# power.net
KiCad netlist of a schematic drawn in Altium Designer
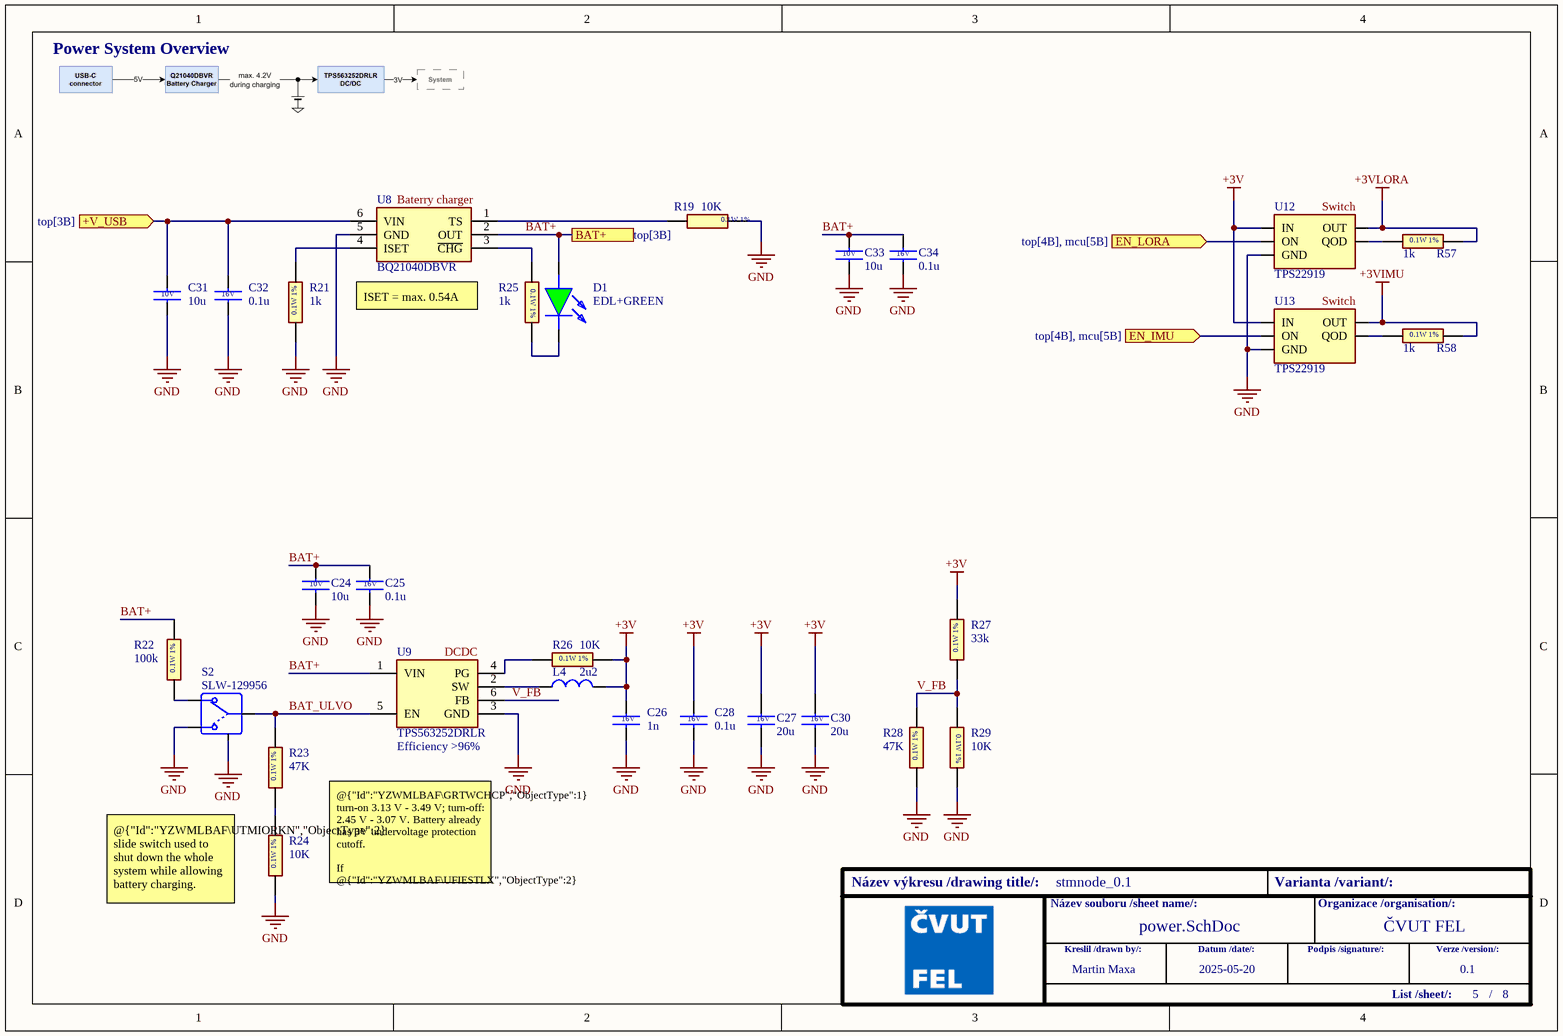
[diagram p0: power.SchDoc]

(export (version "E")
  (design (tool "Eeschema 10.0.6"))
  (components
    (comp (ref "C24")
      (value "10u")
      (footprint "C0603")
      (description "10 VDC, 20 %, X5R")
      (fields
        (field (name "MANUFACTURER_PART_NUMBER") "C0603C106M8PACTU")
        (field (name "MOUSER PART NUMBER") "80-C0603C106M8PACTU")
      )
      (libsource (lib "bch-lib") (part "ECK+10u10V"))
    )
    (comp (ref "C25")
      (value "0.1u")
      (footprint "CAPC1608X95N")
      (description "16V 0.1uF XR7 0603 10%")
      (fields
        (field (name "MANUFACTURER_PART_NUMBER") "C0603C104K4RAC-TU")
        (field (name "MOUSER PART NUMBER") "80-C0603C104K4RAC")
      )
      (libsource (lib "bch-lib") (part "ECK+100n16V"))
    )
    (comp (ref "C26")
      (value "1n")
      (footprint "CAPC1608X87N")
      (description "16 VDC, 10 %, X7R")
      (fields (field (name "MANUFACTURER_PART_NUMBER") "C0603C102K4RECTU"))
      (libsource (lib "bch-lib") (part "ECK+1n16V"))
    )
    (comp (ref "C27")
      (value "20u")
      (footprint "C0603")
      (description "Capacitor")
      (fields
        (field (name "MANUFACTURER_PART_NUMBER") "C0603C200K4HACAUTO")
        (field (name "MOUSER PART NUMBER") "80-C0603C200K4HAUTO")
      )
      (libsource (lib "bch-lib") (part "ECK+20u16V"))
    )
    (comp (ref "C28")
      (value "0.1u")
      (footprint "CAPC1608X95N")
      (description "16V 0.1uF XR7 0603 10%")
      (fields
        (field (name "MANUFACTURER_PART_NUMBER") "C0603C104K4RAC-TU")
        (field (name "MOUSER PART NUMBER") "80-C0603C104K4RAC")
      )
      (libsource (lib "bch-lib") (part "ECK+100n16V"))
    )
    (comp (ref "C30")
      (value "20u")
      (footprint "C0603")
      (description "Capacitor")
      (fields
        (field (name "MANUFACTURER_PART_NUMBER") "C0603C200K4HACAUTO")
        (field (name "MOUSER PART NUMBER") "80-C0603C200K4HAUTO")
      )
      (libsource (lib "bch-lib") (part "ECK+20u16V"))
    )
    (comp (ref "C31")
      (value "10u")
      (footprint "C0603")
      (description "10 VDC, 20 %, X5R")
      (fields
        (field (name "MANUFACTURER_PART_NUMBER") "C0603C106M8PACTU")
        (field (name "MOUSER PART NUMBER") "80-C0603C106M8PACTU")
      )
      (libsource (lib "bch-lib") (part "ECK+10u10V"))
    )
    (comp (ref "C32")
      (value "0.1u")
      (footprint "CAPC1608X95N")
      (description "16V 0.1uF XR7 0603 10%")
      (fields
        (field (name "MANUFACTURER_PART_NUMBER") "C0603C104K4RAC-TU")
        (field (name "MOUSER PART NUMBER") "80-C0603C104K4RAC")
      )
      (libsource (lib "bch-lib") (part "ECK+100n16V"))
    )
    (comp (ref "C33")
      (value "10u")
      (footprint "C0603")
      (description "10 VDC, 20 %, X5R")
      (fields
        (field (name "MANUFACTURER_PART_NUMBER") "C0603C106M8PACTU")
        (field (name "MOUSER PART NUMBER") "80-C0603C106M8PACTU")
      )
      (libsource (lib "bch-lib") (part "ECK+10u10V"))
    )
    (comp (ref "C34")
      (value "0.1u")
      (footprint "CAPC1608X95N")
      (description "16V 0.1uF XR7 0603 10%")
      (fields
        (field (name "MANUFACTURER_PART_NUMBER") "C0603C104K4RAC-TU")
        (field (name "MOUSER PART NUMBER") "80-C0603C104K4RAC")
      )
      (libsource (lib "bch-lib") (part "ECK+100n16V"))
    )
    (comp (ref "D1")
      (value "EDL+GREEN")
      (footprint "LEDM2012X80N")
      (description "LED GREEN,  3.2 V")
      (fields
        (field (name "MANUFACTURER_PART_NUMBER") "150080GS75000")
        (field (name "MOUSER PART NUMBER") "710-150080GS75000")
      )
      (libsource (lib "bch-lib") (part "EDL+GREEN"))
    )
    (comp (ref "L4")
      (value "2u2")
      (footprint "INDPM5752X300N")
      (description "Power Inductors - SMD 2.2uH 20%")
      (fields
        (field (name "MANUFACTURER_PART_NUMBER") "SRP5030TA-2R2M")
        (field (name "MOUSER PART NUMBER") "652-SRP5030TA-2R2M")
      )
      (libsource (lib "bch-lib") (part "EL+2.2u5.5A"))
    )
    (comp (ref "R19")
      (value "10K")
      (footprint "RESC1608X50N")
      (description "Resistor 1%, 0.1W")
      (fields
        (field (name "MANUFACTURER_PART_NUMBER") "CRCW060310K0FKEA")
        (field (name "MOUSER PART NUMBER") "71-CRCW0603-10K-E3")
      )
      (libsource (lib "bch-lib") (part "ER+10K"))
    )
    (comp (ref "R21")
      (value "1k")
      (footprint "RESC1608X50N")
      (description "Resistor 1%, 0.1W")
      (fields
        (field (name "MANUFACTURER_PART_NUMBER") "CRCW06031K00FKEA")
        (field (name "MOUSER PART NUMBER") "71-CRCW0603-1.0K-E3")
      )
      (libsource (lib "") (part "ER+1K_1"))
    )
    (comp (ref "R22")
      (value "100k")
      (footprint "RESC1608X55N")
      (description "Thick Film Resistors 0603 - SMD 1/10Watt 100Kohms 1% Commercial Use")
      (fields
        (field (name "MANUFACTURER_PART_NUMBER") "AC0603FR-10100KL")
        (field (name "MOUSER PART NUMBER") "603-AC0603FR-10100KL")
      )
      (libsource (lib "bch-lib") (part "ER+100k"))
    )
    (comp (ref "R23")
      (value "47K")
      (footprint "RESC1608X50N")
      (description "Resistor 1%, 0.1W")
      (fields
        (field (name "MANUFACTURER_PART_NUMBER") "CRCW060347K0FKEA")
        (field (name "MOUSER PART NUMBER") "71-CRCW0603-47K-E3")
      )
      (libsource (lib "bch-lib") (part "ER+47K"))
    )
    (comp (ref "R24")
      (value "10K")
      (footprint "RESC1608X50N")
      (description "Resistor 1%, 0.1W")
      (fields
        (field (name "MANUFACTURER_PART_NUMBER") "CRCW060310K0FKEA")
        (field (name "MOUSER PART NUMBER") "71-CRCW0603-10K-E3")
      )
      (libsource (lib "") (part "ER+10K_2"))
    )
    (comp (ref "R25")
      (value "1k")
      (footprint "RESC1608X50N")
      (description "Resistor 1%, 0.1W")
      (fields
        (field (name "MANUFACTURER_PART_NUMBER") "CRCW06031K00FKEA")
        (field (name "MOUSER PART NUMBER") "71-CRCW0603-1.0K-E3")
      )
      (libsource (lib "bch-lib") (part "ER+1K"))
    )
    (comp (ref "R26")
      (value "10K")
      (footprint "RESC1608X50N")
      (description "Resistor 1%, 0.1W")
      (fields
        (field (name "MANUFACTURER_PART_NUMBER") "CRCW060310K0FKEA")
        (field (name "MOUSER PART NUMBER") "71-CRCW0603-10K-E3")
      )
      (libsource (lib "") (part "ER+10K_1"))
    )
    (comp (ref "R27")
      (value "33k")
      (footprint "RESC1608X55N")
      (description "Thick Film Resistors - SMD General Purpose Chip Resistor 0603, 33kOhms, 1%, 1/10W")
      (fields
        (field (name "MANUFACTURER_PART_NUMBER") "RC0603FR-1333KL")
        (field (name "MOUSER PART NUMBER") "603-RC0603FR-1333KL")
      )
      (libsource (lib "bch-lib") (part "ER+33k"))
    )
    (comp (ref "R28")
      (value "47K")
      (footprint "RESC1608X50N")
      (description "Resistor 1%, 0.1W")
      (fields
        (field (name "MANUFACTURER_PART_NUMBER") "CRCW060347K0FKEA")
        (field (name "MOUSER PART NUMBER") "71-CRCW0603-47K-E3")
      )
      (libsource (lib "bch-lib") (part "ER+47K"))
    )
    (comp (ref "R29")
      (value "10K")
      (footprint "RESC1608X50N")
      (description "Resistor 1%, 0.1W")
      (fields
        (field (name "MANUFACTURER_PART_NUMBER") "CRCW060310K0FKEA")
        (field (name "MOUSER PART NUMBER") "71-CRCW0603-10K-E3")
      )
      (libsource (lib "bch-lib") (part "ER+10K"))
    )
    (comp (ref "R57")
      (value "1k")
      (footprint "RESC1608X50N")
      (description "Resistor 1%, 0.1W")
      (fields
        (field (name "MANUFACTURER_PART_NUMBER") "CRCW06031K00FKEA")
        (field (name "MOUSER PART NUMBER") "71-CRCW0603-1.0K-E3")
      )
      (libsource (lib "") (part "ER+1K_2"))
    )
    (comp (ref "R58")
      (value "1k")
      (footprint "RESC1608X50N")
      (description "Resistor 1%, 0.1W")
      (fields
        (field (name "MANUFACTURER_PART_NUMBER") "CRCW06031K00FKEA")
        (field (name "MOUSER PART NUMBER") "71-CRCW0603-1.0K-E3")
      )
      (libsource (lib "") (part "ER+1K_2"))
    )
    (comp (ref "S2")
      (value "SLW-129956")
      (footprint "SLW1299564ARAND")
      (description "Slide Switch, Right Angle, max. 50 VDC, max. 300 mA, ON - ON")
      (fields
        (field (name "MANUFACTURER_PART_NUMBER") "SLW-129956-4A-RA-N-D")
        (field (name "MOUSER PART NUMBER") "179-SLW1299564ARAND")
      )
      (libsource (lib "bch-lib") (part "ESW-SLW-129956"))
    )
    (comp (ref "U8")
      (value "BQ21040DBVR")
      (footprint "SOT95P280X145-6N")
      (description "Battery Management 1-cell 0.8-A Li-ion and Li-polymer batt A 595-BQ21040DBVT")
      (fields (field (name "MOUSER PART NUMBER") "595-BQ21040DBVR"))
      (libsource (lib "bch-lib") (part "EU+BQ21040DBVR"))
    )
    (comp (ref "U9")
      (value "TPS563252DRLR")
      (footprint "SOTFL50P160X60-6N")
      (description "Switching Voltage Regulators 3-V to 17-V input vo ltage 3-A 1.2-Mhz")
      (fields (field (name "MOUSER PART NUMBER") "595-TPS563252DRLR"))
      (libsource (lib "bch-lib") (part "EU+TPS563252DRLR"))
    )
    (comp (ref "U12")
      (value "TPS22919")
      (footprint "SOT65P210X110-6N")
      (description "Power Switch ICs - Power Distribution 1-ch 5.5V 1.5A 90 mOhm self-protected AE")
      (fields
        (field (name "MANUFACTURER_PART_NUMBER") "TPS22919QDCKRQ1")
        (field (name "MOUSER PART NUMBER") "595-TPS22919QDCKRQ1")
      )
      (libsource (lib "bch-lib") (part "EU+TPS22919"))
    )
    (comp (ref "U13")
      (value "TPS22919")
      (footprint "SOT65P210X110-6N")
      (description "Power Switch ICs - Power Distribution 1-ch 5.5V 1.5A 90 mOhm self-protected AE")
      (fields
        (field (name "MANUFACTURER_PART_NUMBER") "TPS22919QDCKRQ1")
        (field (name "MOUSER PART NUMBER") "595-TPS22919QDCKRQ1")
      )
      (libsource (lib "bch-lib") (part "EU+TPS22919"))
    )
  )
  (nets
    (net (code "1") (name "+3V") (class "Default")
      (node (ref "C26") (pin "1") (pinfunction "1_1") (pintype "passive"))
      (node (ref "C27") (pin "1") (pinfunction "1_1") (pintype "passive"))
      (node (ref "C28") (pin "1") (pinfunction "1_1") (pintype "passive"))
      (node (ref "C30") (pin "1") (pinfunction "1_1") (pintype "passive"))
      (node (ref "L4") (pin "2") (pinfunction "2_2") (pintype "passive"))
      (node (ref "R26") (pin "2") (pinfunction "2_2") (pintype "passive"))
      (node (ref "R27") (pin "2") (pinfunction "2_2") (pintype "passive"))
      (node (ref "U12") (pin "1") (pinfunction "IN_1") (pintype "passive"))
      (node (ref "U13") (pin "1") (pinfunction "IN_1") (pintype "passive"))
    )
    (net (code "2") (name "+3VIMU") (class "Default")
      (node (ref "R58") (pin "2") (pinfunction "2_2") (pintype "passive"))
      (node (ref "U13") (pin "6") (pinfunction "OUT_6") (pintype "passive"))
    )
    (net (code "3") (name "+3VLORA") (class "Default")
      (node (ref "R57") (pin "2") (pinfunction "2_2") (pintype "passive"))
      (node (ref "U12") (pin "6") (pinfunction "OUT_6") (pintype "passive"))
    )
    (net (code "4") (name "/+V_USB") (class "Default")
      (node (ref "C31") (pin "1") (pinfunction "1_1") (pintype "passive"))
      (node (ref "C32") (pin "1") (pinfunction "1_1") (pintype "passive"))
      (node (ref "U8") (pin "6") (pinfunction "VIN_6") (pintype "passive"))
    )
    (net (code "5") (name "/BAT+") (class "Default")
      (node (ref "C24") (pin "1") (pinfunction "1_1") (pintype "passive"))
      (node (ref "C25") (pin "1") (pinfunction "1_1") (pintype "passive"))
      (node (ref "C33") (pin "1") (pinfunction "1_1") (pintype "passive"))
      (node (ref "C34") (pin "1") (pinfunction "1_1") (pintype "passive"))
      (node (ref "D1") (pin "1") (pinfunction "K_1") (pintype "passive"))
      (node (ref "R22") (pin "2") (pinfunction "2_2") (pintype "passive"))
      (node (ref "U8") (pin "2") (pinfunction "OUT_2") (pintype "passive"))
      (node (ref "U9") (pin "1") (pinfunction "VIN_1") (pintype "passive"))
    )
    (net (code "6") (name "/BAT_ULVO") (class "Default")
      (node (ref "R23") (pin "2") (pinfunction "2_2") (pintype "passive"))
      (node (ref "S2") (pin "2") (pinfunction "COM_2") (pintype "passive"))
      (node (ref "U9") (pin "5") (pinfunction "EN_5") (pintype "passive"))
    )
    (net (code "7") (name "/EN_IMU") (class "Default")
      (node (ref "U13") (pin "3") (pinfunction "ON_3") (pintype "passive"))
    )
    (net (code "8") (name "/EN_LORA") (class "Default")
      (node (ref "U12") (pin "3") (pinfunction "ON_3") (pintype "passive"))
    )
    (net (code "9") (name "/V_FB") (class "Default")
      (node (ref "R27") (pin "1") (pinfunction "1_1") (pintype "passive"))
      (node (ref "R28") (pin "2") (pinfunction "2_2") (pintype "passive"))
      (node (ref "R29") (pin "1") (pinfunction "1_1") (pintype "passive"))
      (node (ref "U9") (pin "6") (pinfunction "FB_6") (pintype "passive"))
    )
    (net (code "10") (name "GND") (class "Default")
      (node (ref "C24") (pin "2") (pinfunction "2_2") (pintype "passive"))
      (node (ref "C25") (pin "2") (pinfunction "2_2") (pintype "passive"))
      (node (ref "C26") (pin "2") (pinfunction "2_2") (pintype "passive"))
      (node (ref "C27") (pin "2") (pinfunction "2_2") (pintype "passive"))
      (node (ref "C28") (pin "2") (pinfunction "2_2") (pintype "passive"))
      (node (ref "C30") (pin "2") (pinfunction "2_2") (pintype "passive"))
      (node (ref "C31") (pin "2") (pinfunction "2_2") (pintype "passive"))
      (node (ref "C32") (pin "2") (pinfunction "2_2") (pintype "passive"))
      (node (ref "C33") (pin "2") (pinfunction "2_2") (pintype "passive"))
      (node (ref "C34") (pin "2") (pinfunction "2_2") (pintype "passive"))
      (node (ref "R19") (pin "1") (pinfunction "1_1") (pintype "passive"))
      (node (ref "R21") (pin "1") (pinfunction "1_1") (pintype "passive"))
      (node (ref "R24") (pin "1") (pinfunction "1_1") (pintype "passive"))
      (node (ref "R28") (pin "1") (pinfunction "1_1") (pintype "passive"))
      (node (ref "R29") (pin "2") (pinfunction "2_2") (pintype "passive"))
      (node (ref "S2") (pin "3") (pinfunction "NO_3") (pintype "passive"))
      (node (ref "S2") (pin "4") (pinfunction "MH1_4") (pintype "passive"))
      (node (ref "U12") (pin "2") (pinfunction "GND_2") (pintype "passive"))
      (node (ref "U13") (pin "2") (pinfunction "GND_2") (pintype "passive"))
      (node (ref "U8") (pin "5") (pinfunction "GND_5") (pintype "power_in"))
      (node (ref "U9") (pin "3") (pinfunction "GND_3") (pintype "passive"))
    )
    (net (code "11") (name "Net-(D1-A)") (class "Default")
      (node (ref "D1") (pin "2") (pinfunction "A_2") (pintype "passive"))
      (node (ref "R25") (pin "2") (pinfunction "2_2") (pintype "passive"))
    )
    (net (code "12") (name "Net-(R22-Pad1)") (class "Default")
      (node (ref "R22") (pin "1") (pinfunction "1_1") (pintype "passive"))
      (node (ref "S2") (pin "1") (pinfunction "NO_1") (pintype "passive"))
    )
    (net (code "13") (name "Net-(R23-Pad1)") (class "Default")
      (node (ref "R23") (pin "1") (pinfunction "1_1") (pintype "passive"))
      (node (ref "R24") (pin "2") (pinfunction "2_2") (pintype "passive"))
    )
    (net (code "14") (name "Net-(U8-ISET)") (class "Default")
      (node (ref "R21") (pin "2") (pinfunction "2_2") (pintype "passive"))
      (node (ref "U8") (pin "4") (pinfunction "ISET_4") (pintype "passive"))
    )
    (net (code "15") (name "Net-(U8-TS)") (class "Default")
      (node (ref "R19") (pin "2") (pinfunction "2_2") (pintype "passive"))
      (node (ref "U8") (pin "1") (pinfunction "TS_1") (pintype "passive"))
    )
    (net (code "16") (name "Net-(U8-~{CHG})") (class "Default")
      (node (ref "R25") (pin "1") (pinfunction "1_1") (pintype "passive"))
      (node (ref "U8") (pin "3") (pinfunction "~{CHG}_3") (pintype "passive"))
    )
    (net (code "17") (name "Net-(U9-PG)") (class "Default")
      (node (ref "R26") (pin "1") (pinfunction "1_1") (pintype "passive"))
      (node (ref "U9") (pin "4") (pinfunction "PG_4") (pintype "passive"))
    )
    (net (code "18") (name "Net-(U9-SW)") (class "Default")
      (node (ref "L4") (pin "1") (pinfunction "1_1") (pintype "passive"))
      (node (ref "U9") (pin "2") (pinfunction "SW_2") (pintype "passive"))
    )
    (net (code "19") (name "Net-(U12-QOD)") (class "Default")
      (node (ref "R57") (pin "1") (pinfunction "1_1") (pintype "passive"))
      (node (ref "U12") (pin "5") (pinfunction "QOD_5") (pintype "passive"))
    )
    (net (code "20") (name "Net-(U13-QOD)") (class "Default")
      (node (ref "R58") (pin "1") (pinfunction "1_1") (pintype "passive"))
      (node (ref "U13") (pin "5") (pinfunction "QOD_5") (pintype "passive"))
    )
  )
)
